# BMP280-Breakout_v10.net
KiCad netlist of a schematic drawn in EAGLE
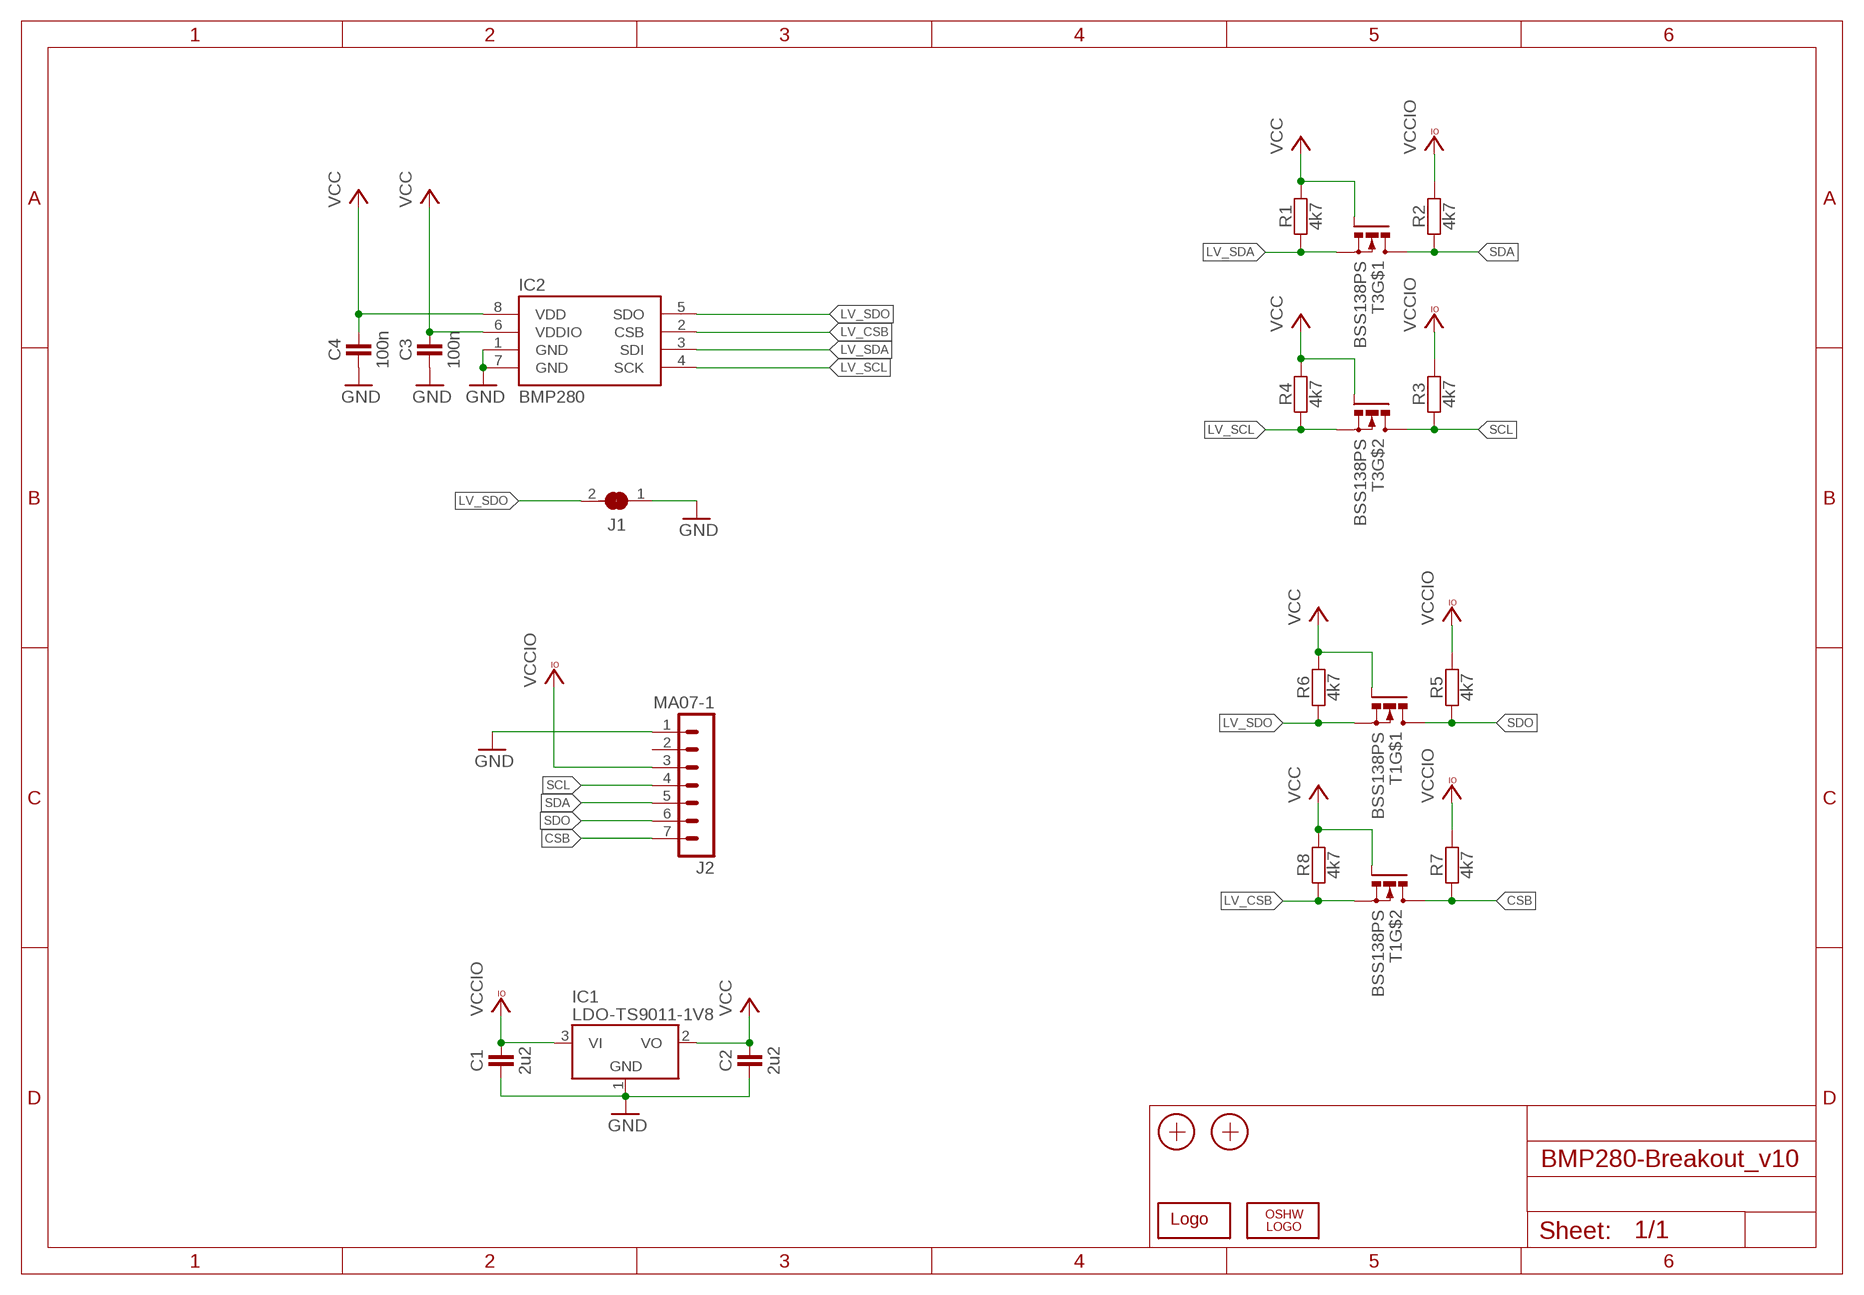
[diagram p0: schematic, sheet 1]

(export (version "E")
  (design (tool "Eeschema 10.0.6"))
  (components
    (comp (ref "C1")
      (value "2u2")
      (footprint "eagle-import:R0402")
      (libsource (lib "eagle-import") (part "CAPACITOR-C0402"))
    )
    (comp (ref "C2")
      (value "2u2")
      (footprint "eagle-import:R0402")
      (libsource (lib "eagle-import") (part "CAPACITOR-C0402"))
    )
    (comp (ref "C3")
      (value "100n")
      (footprint "eagle-import:R0402")
      (libsource (lib "eagle-import") (part "CAPACITOR-C0402"))
    )
    (comp (ref "C4")
      (value "100n")
      (footprint "eagle-import:R0402")
      (libsource (lib "eagle-import") (part "CAPACITOR-C0402"))
    )
    (comp (ref "IC1")
      (value "LDO-TS9011-1V8")
      (footprint "eagle-import:SOT23")
      (libsource (lib "eagle-import") (part "LDO-TS9011-3V3"))
    )
    (comp (ref "IC2")
      (value "BMP280")
      (footprint "eagle-import:LGA")
      (libsource (lib "eagle-import") (part "BMP280"))
    )
    (comp (ref "J1")
      (value "JUMPER2")
      (footprint "eagle-import:JUMPER2")
      (libsource (lib "eagle-import") (part "JUMPER2"))
    )
    (comp (ref "J2")
      (value "MA07-1")
      (footprint "eagle-import:MA07-1")
      (libsource (lib "eagle-import") (part "MA07-1"))
    )
    (comp (ref "LOGO1")
      (value "LOGO-S_PLACE_M")
      (footprint "eagle-import:SPARK_TPLACE_M")
      (libsource (lib "eagle-import") (part "LOGO-S_PLACE_M"))
    )
    (comp (ref "LOGO2")
      (value "OSHW_LOGOX0070")
      (footprint "eagle-import:OSHW_6X70")
      (libsource (lib "eagle-import") (part "OSHW_LOGOX0070"))
    )
    (comp (ref "R1")
      (value "4k7")
      (footprint "eagle-import:R0402")
      (libsource (lib "eagle-import") (part "RESISTOR-R0402"))
    )
    (comp (ref "R2")
      (value "4k7")
      (footprint "eagle-import:R0402")
      (libsource (lib "eagle-import") (part "RESISTOR-R0402"))
    )
    (comp (ref "R3")
      (value "4k7")
      (footprint "eagle-import:R0402")
      (libsource (lib "eagle-import") (part "RESISTOR-R0402"))
    )
    (comp (ref "R4")
      (value "4k7")
      (footprint "eagle-import:R0402")
      (libsource (lib "eagle-import") (part "RESISTOR-R0402"))
    )
    (comp (ref "R5")
      (value "4k7")
      (footprint "eagle-import:R0402")
      (libsource (lib "eagle-import") (part "RESISTOR-R0402"))
    )
    (comp (ref "R6")
      (value "4k7")
      (footprint "eagle-import:R0402")
      (libsource (lib "eagle-import") (part "RESISTOR-R0402"))
    )
    (comp (ref "R7")
      (value "4k7")
      (footprint "eagle-import:R0402")
      (libsource (lib "eagle-import") (part "RESISTOR-R0402"))
    )
    (comp (ref "R8")
      (value "4k7")
      (footprint "eagle-import:R0402")
      (libsource (lib "eagle-import") (part "RESISTOR-R0402"))
    )
    (comp (ref "T1")
      (value "BSS138PS")
      (footprint "eagle-import:SOT363")
      (libsource (lib "eagle-import") (part "BSS138PS"))
    )
    (comp (ref "T3")
      (value "BSS138PS")
      (footprint "eagle-import:SOT363")
      (libsource (lib "eagle-import") (part "BSS138PS"))
    )
    (comp (ref "X1")
      (value "PASSER-07")
      (footprint "eagle-import:PASSER_07MM")
      (libsource (lib "eagle-import") (part "PASSER-07"))
    )
    (comp (ref "X2")
      (value "PASSER-07")
      (footprint "eagle-import:PASSER_07MM")
      (libsource (lib "eagle-import") (part "PASSER-07"))
    )
  )
  (nets
    (net (code "1") (name "CSB") (class "Default")
      (node (ref "J2") (pin "7") (pinfunction "7_7") (pintype "passive"))
      (node (ref "R7") (pin "1") (pinfunction "1_1") (pintype "passive"))
      (node (ref "T1") (pin "3") (pinfunction "D_3") (pintype "passive"))
    )
    (net (code "2") (name "GND") (class "Default")
      (node (ref "C1") (pin "1") (pinfunction "1_1") (pintype "passive"))
      (node (ref "C2") (pin "1") (pinfunction "1_1") (pintype "passive"))
      (node (ref "C3") (pin "1") (pinfunction "1_1") (pintype "passive"))
      (node (ref "C4") (pin "1") (pinfunction "1_1") (pintype "passive"))
      (node (ref "IC1") (pin "1") (pinfunction "GND_1") (pintype "passive"))
      (node (ref "IC2") (pin "1") (pinfunction "GND_1") (pintype "power_in"))
      (node (ref "IC2") (pin "7") (pinfunction "GND_7") (pintype "power_in"))
      (node (ref "J1") (pin "1") (pinfunction "1_1") (pintype "passive"))
      (node (ref "J2") (pin "1") (pinfunction "1_1") (pintype "passive"))
    )
    (net (code "3") (name "LV_CSB") (class "Default")
      (node (ref "IC2") (pin "2") (pinfunction "CSB_2") (pintype "input"))
      (node (ref "R8") (pin "1") (pinfunction "1_1") (pintype "passive"))
      (node (ref "T1") (pin "4") (pinfunction "S_4") (pintype "passive"))
    )
    (net (code "4") (name "LV_SCL") (class "Default")
      (node (ref "IC2") (pin "4") (pinfunction "SCK_4") (pintype "input"))
      (node (ref "R4") (pin "1") (pinfunction "1_1") (pintype "passive"))
      (node (ref "T3") (pin "4") (pinfunction "S_4") (pintype "passive"))
    )
    (net (code "5") (name "LV_SDA") (class "Default")
      (node (ref "IC2") (pin "3") (pinfunction "SDI_3") (pintype "bidirectional"))
      (node (ref "R1") (pin "1") (pinfunction "1_1") (pintype "passive"))
      (node (ref "T3") (pin "1") (pinfunction "S_1") (pintype "passive"))
    )
    (net (code "6") (name "LV_SDO") (class "Default")
      (node (ref "IC2") (pin "5") (pinfunction "SDO_5") (pintype "bidirectional"))
      (node (ref "J1") (pin "2") (pinfunction "2_2") (pintype "passive"))
      (node (ref "R6") (pin "1") (pinfunction "1_1") (pintype "passive"))
      (node (ref "T1") (pin "1") (pinfunction "S_1") (pintype "passive"))
    )
    (net (code "7") (name "SCL") (class "Default")
      (node (ref "J2") (pin "4") (pinfunction "4_4") (pintype "passive"))
      (node (ref "R3") (pin "1") (pinfunction "1_1") (pintype "passive"))
      (node (ref "T3") (pin "3") (pinfunction "D_3") (pintype "passive"))
    )
    (net (code "8") (name "SDA") (class "Default")
      (node (ref "J2") (pin "5") (pinfunction "5_5") (pintype "passive"))
      (node (ref "R2") (pin "1") (pinfunction "1_1") (pintype "passive"))
      (node (ref "T3") (pin "6") (pinfunction "D_6") (pintype "passive"))
    )
    (net (code "9") (name "SDO") (class "Default")
      (node (ref "J2") (pin "6") (pinfunction "6_6") (pintype "passive"))
      (node (ref "R5") (pin "1") (pinfunction "1_1") (pintype "passive"))
      (node (ref "T1") (pin "6") (pinfunction "D_6") (pintype "passive"))
    )
    (net (code "10") (name "VCC") (class "Default")
      (node (ref "C2") (pin "2") (pinfunction "2_2") (pintype "passive"))
      (node (ref "C3") (pin "2") (pinfunction "2_2") (pintype "passive"))
      (node (ref "C4") (pin "2") (pinfunction "2_2") (pintype "passive"))
      (node (ref "IC1") (pin "2") (pinfunction "VO_2") (pintype "passive"))
      (node (ref "IC2") (pin "6") (pinfunction "VDDIO_6") (pintype "input"))
      (node (ref "IC2") (pin "8") (pinfunction "VDD_8") (pintype "power_in"))
      (node (ref "R1") (pin "2") (pinfunction "2_2") (pintype "passive"))
      (node (ref "R4") (pin "2") (pinfunction "2_2") (pintype "passive"))
      (node (ref "R6") (pin "2") (pinfunction "2_2") (pintype "passive"))
      (node (ref "R8") (pin "2") (pinfunction "2_2") (pintype "passive"))
      (node (ref "T1") (pin "2") (pinfunction "G_2") (pintype "passive"))
      (node (ref "T1") (pin "5") (pinfunction "G_5") (pintype "passive"))
      (node (ref "T3") (pin "2") (pinfunction "G_2") (pintype "passive"))
      (node (ref "T3") (pin "5") (pinfunction "G_5") (pintype "passive"))
    )
    (net (code "11") (name "VCCIO") (class "Default")
      (node (ref "C1") (pin "2") (pinfunction "2_2") (pintype "passive"))
      (node (ref "IC1") (pin "3") (pinfunction "VI_3") (pintype "input"))
      (node (ref "J2") (pin "3") (pinfunction "3_3") (pintype "passive"))
      (node (ref "R2") (pin "2") (pinfunction "2_2") (pintype "passive"))
      (node (ref "R3") (pin "2") (pinfunction "2_2") (pintype "passive"))
      (node (ref "R5") (pin "2") (pinfunction "2_2") (pintype "passive"))
      (node (ref "R7") (pin "2") (pinfunction "2_2") (pintype "passive"))
    )
    (net (code "12") (name "unconnected-(J2-Pad2)") (class "Default")
      (node (ref "J2") (pin "2") (pinfunction "2_2") (pintype "passive"))
    )
  )
)
